# esp.net
KiCad netlist of a schematic drawn in EAGLE
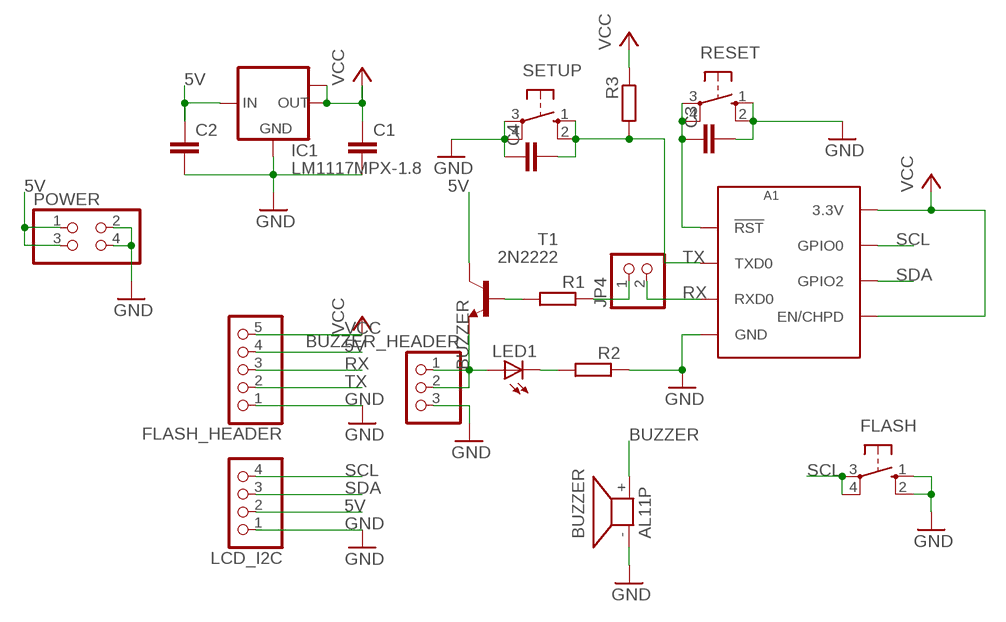
[diagram p0: schematic, sheet 1]

(export (version "E")
  (design (tool "Eeschema 10.0.6"))
  (components
    (comp (ref "A1")
      (value "ESP8266_ESP-01")
      (footprint "eagle-import:ESP8266_ESP-01_NO-SILKSCREEN")
      (libsource (lib "eagle-import") (part "ESP8266_ESP-?01"))
    )
    (comp (ref "BUZZER")
      (value "AL11P")
      (footprint "eagle-import:AL11P")
      (libsource (lib "eagle-import") (part "AL11P"))
    )
    (comp (ref "BUZZER_HEADER")
      (value "PINHD-1X3")
      (footprint "eagle-import:1X03")
      (libsource (lib "eagle-import") (part "PINHD-1X3"))
    )
    (comp (ref "C1")
      (value "C-EU050-025X075")
      (footprint "eagle-import:C050-025X075")
      (libsource (lib "eagle-import") (part "C-EU050-025X075"))
    )
    (comp (ref "C2")
      (value "C-EU050-025X075")
      (footprint "eagle-import:C050-025X075")
      (libsource (lib "eagle-import") (part "C-EU050-025X075"))
    )
    (comp (ref "C3")
      (value "C-EU050-025X075")
      (footprint "eagle-import:C050-025X075")
      (libsource (lib "eagle-import") (part "C-EU050-025X075"))
    )
    (comp (ref "C4")
      (value "C-EU050-025X075")
      (footprint "eagle-import:C050-025X075")
      (libsource (lib "eagle-import") (part "C-EU050-025X075"))
    )
    (comp (ref "FLASH")
      (value "10-XX")
      (footprint "eagle-import:B3F-10XX")
      (fields (field (name "MPN") "B3F-1000"))
      (libsource (lib "eagle-import") (part "10-XX"))
    )
    (comp (ref "FLASH_HEADER")
      (value "PINHD-1X5")
      (footprint "eagle-import:1X05")
      (libsource (lib "eagle-import") (part "PINHD-1X5"))
    )
    (comp (ref "IC1")
      (value "LM1117MPX-1.8")
      (footprint "eagle-import:SOT223")
      (libsource (lib "eagle-import") (part "LM1117MPX-1.8"))
    )
    (comp (ref "JP4")
      (value "PINHD-1X2")
      (footprint "eagle-import:1X02")
      (libsource (lib "eagle-import") (part "PINHD-1X2"))
    )
    (comp (ref "LCD_I2C")
      (value "PINHD-1X4")
      (footprint "eagle-import:1X04")
      (libsource (lib "eagle-import") (part "PINHD-1X4"))
    )
    (comp (ref "LED1")
      (value "LED5MM")
      (footprint "eagle-import:LED5MM")
      (libsource (lib "eagle-import") (part "LED5MM"))
    )
    (comp (ref "POWER")
      (value "PINHD-2X2")
      (footprint "eagle-import:2X02")
      (libsource (lib "eagle-import") (part "PINHD-2X2"))
    )
    (comp (ref "R1")
      (value "R-EU_0207/10")
      (footprint "eagle-import:0207_10")
      (libsource (lib "eagle-import") (part "R-EU_0207/10"))
    )
    (comp (ref "R2")
      (value "R-EU_0207/10")
      (footprint "eagle-import:0207_10")
      (libsource (lib "eagle-import") (part "R-EU_0207/10"))
    )
    (comp (ref "R3")
      (value "R-EU_0207/10")
      (footprint "eagle-import:0207_10")
      (libsource (lib "eagle-import") (part "R-EU_0207/10"))
    )
    (comp (ref "RESET")
      (value "10-XX")
      (footprint "eagle-import:B3F-10XX")
      (fields (field (name "MPN") "B3F-1000"))
      (libsource (lib "eagle-import") (part "10-XX"))
    )
    (comp (ref "SETUP")
      (value "10-XX")
      (footprint "eagle-import:B3F-10XX")
      (fields (field (name "MPN") "B3F-1000"))
      (libsource (lib "eagle-import") (part "10-XX"))
    )
    (comp (ref "T1")
      (value "2N2222")
      (footprint "eagle-import:TO18")
      (libsource (lib "eagle-import") (part "2N2222"))
    )
  )
  (nets
    (net (code "1") (name "/5V") (class "Default")
      (node (ref "C2") (pin "1") (pinfunction "1_1") (pintype "passive"))
      (node (ref "FLASH_HEADER") (pin "4") (pinfunction "4_4") (pintype "passive"))
      (node (ref "IC1") (pin "3") (pinfunction "IN_3") (pintype "input"))
      (node (ref "LCD_I2C") (pin "2") (pinfunction "2_2") (pintype "passive"))
      (node (ref "POWER") (pin "1") (pinfunction "1_1") (pintype "passive"))
      (node (ref "POWER") (pin "3") (pinfunction "3_3") (pintype "passive"))
      (node (ref "T1") (pin "3") (pinfunction "C_3") (pintype "passive"))
    )
    (net (code "2") (name "/BUZZER") (class "Default")
      (node (ref "BUZZER") (pin "+") (pinfunction "2_+") (pintype "passive"))
      (node (ref "BUZZER_HEADER") (pin "1") (pinfunction "1_1") (pintype "passive"))
      (node (ref "BUZZER_HEADER") (pin "2") (pinfunction "2_2") (pintype "passive"))
      (node (ref "LED1") (pin "A") (pinfunction "A_A") (pintype "passive"))
      (node (ref "T1") (pin "1") (pinfunction "E_1") (pintype "passive"))
    )
    (net (code "3") (name "/RX") (class "Default")
      (node (ref "A1") (pin "RX") (pinfunction "RXD0_RX") (pintype "bidirectional"))
      (node (ref "FLASH_HEADER") (pin "3") (pinfunction "3_3") (pintype "passive"))
      (node (ref "JP4") (pin "2") (pinfunction "2_2") (pintype "passive"))
    )
    (net (code "4") (name "/SCL") (class "Default")
      (node (ref "A1") (pin "GPIO0") (pinfunction "GPIO0_GPIO0") (pintype "bidirectional"))
      (node (ref "FLASH") (pin "3") (pinfunction "P_3") (pintype "passive"))
      (node (ref "FLASH") (pin "4") (pinfunction "P1_4") (pintype "passive"))
      (node (ref "LCD_I2C") (pin "4") (pinfunction "4_4") (pintype "passive"))
    )
    (net (code "5") (name "/SDA") (class "Default")
      (node (ref "A1") (pin "GPIO2") (pinfunction "GPIO2_GPIO2") (pintype "bidirectional"))
      (node (ref "LCD_I2C") (pin "3") (pinfunction "3_3") (pintype "passive"))
    )
    (net (code "6") (name "/TX") (class "Default")
      (node (ref "A1") (pin "TX") (pinfunction "TXD0_TX") (pintype "bidirectional"))
      (node (ref "C4") (pin "2") (pinfunction "2_2") (pintype "passive"))
      (node (ref "FLASH_HEADER") (pin "2") (pinfunction "2_2") (pintype "passive"))
      (node (ref "R3") (pin "2") (pinfunction "2_2") (pintype "passive"))
      (node (ref "SETUP") (pin "1") (pinfunction "S_1") (pintype "passive"))
      (node (ref "SETUP") (pin "2") (pinfunction "S1_2") (pintype "passive"))
    )
    (net (code "7") (name "GND") (class "Default")
      (node (ref "A1") (pin "GND") (pinfunction "GND_GND") (pintype "passive"))
      (node (ref "BUZZER") (pin "-") (pinfunction "1_-") (pintype "passive"))
      (node (ref "BUZZER_HEADER") (pin "3") (pinfunction "3_3") (pintype "passive"))
      (node (ref "C1") (pin "2") (pinfunction "2_2") (pintype "passive"))
      (node (ref "C2") (pin "2") (pinfunction "2_2") (pintype "passive"))
      (node (ref "C3") (pin "2") (pinfunction "2_2") (pintype "passive"))
      (node (ref "C4") (pin "1") (pinfunction "1_1") (pintype "passive"))
      (node (ref "FLASH") (pin "1") (pinfunction "S_1") (pintype "passive"))
      (node (ref "FLASH") (pin "2") (pinfunction "S1_2") (pintype "passive"))
      (node (ref "FLASH_HEADER") (pin "1") (pinfunction "1_1") (pintype "passive"))
      (node (ref "IC1") (pin "1") (pinfunction "GND_1") (pintype "input"))
      (node (ref "LCD_I2C") (pin "1") (pinfunction "1_1") (pintype "passive"))
      (node (ref "POWER") (pin "2") (pinfunction "2_2") (pintype "passive"))
      (node (ref "POWER") (pin "4") (pinfunction "4_4") (pintype "passive"))
      (node (ref "R2") (pin "1") (pinfunction "1_1") (pintype "passive"))
      (node (ref "RESET") (pin "1") (pinfunction "S_1") (pintype "passive"))
      (node (ref "RESET") (pin "2") (pinfunction "S1_2") (pintype "passive"))
      (node (ref "SETUP") (pin "3") (pinfunction "P_3") (pintype "passive"))
      (node (ref "SETUP") (pin "4") (pinfunction "P1_4") (pintype "passive"))
    )
    (net (code "8") (name "Net-(A1-~{RST})") (class "Default")
      (node (ref "A1") (pin "RST") (pinfunction "~{RST}_RST") (pintype "bidirectional"))
      (node (ref "C3") (pin "1") (pinfunction "1_1") (pintype "passive"))
      (node (ref "RESET") (pin "3") (pinfunction "P_3") (pintype "passive"))
      (node (ref "RESET") (pin "4") (pinfunction "P1_4") (pintype "passive"))
    )
    (net (code "9") (name "Net-(JP4-Pad1)") (class "Default")
      (node (ref "JP4") (pin "1") (pinfunction "1_1") (pintype "passive"))
      (node (ref "R1") (pin "1") (pinfunction "1_1") (pintype "passive"))
    )
    (net (code "10") (name "Net-(LED1-C)") (class "Default")
      (node (ref "LED1") (pin "K") (pinfunction "C_K") (pintype "passive"))
      (node (ref "R2") (pin "2") (pinfunction "2_2") (pintype "passive"))
    )
    (net (code "11") (name "Net-(T1-B)") (class "Default")
      (node (ref "R1") (pin "2") (pinfunction "2_2") (pintype "passive"))
      (node (ref "T1") (pin "2") (pinfunction "B_2") (pintype "passive"))
    )
    (net (code "12") (name "VCC") (class "Default")
      (node (ref "A1") (pin "3V3") (pinfunction "3.3V_3V3") (pintype "passive"))
      (node (ref "A1") (pin "EN/CH_PD") (pinfunction "EN/CHPD_EN/CH_PD") (pintype "bidirectional"))
      (node (ref "C1") (pin "1") (pinfunction "1_1") (pintype "passive"))
      (node (ref "FLASH_HEADER") (pin "5") (pinfunction "5_5") (pintype "passive"))
      (node (ref "IC1") (pin "2") (pinfunction "OUT_2") (pintype "passive"))
      (node (ref "IC1") (pin "TAB") (pinfunction "OUT1_TAB") (pintype "passive"))
      (node (ref "R3") (pin "1") (pinfunction "1_1") (pintype "passive"))
    )
  )
)
